# flight_cont_card.net
KiCad netlist of a schematic drawn in Altium Designer
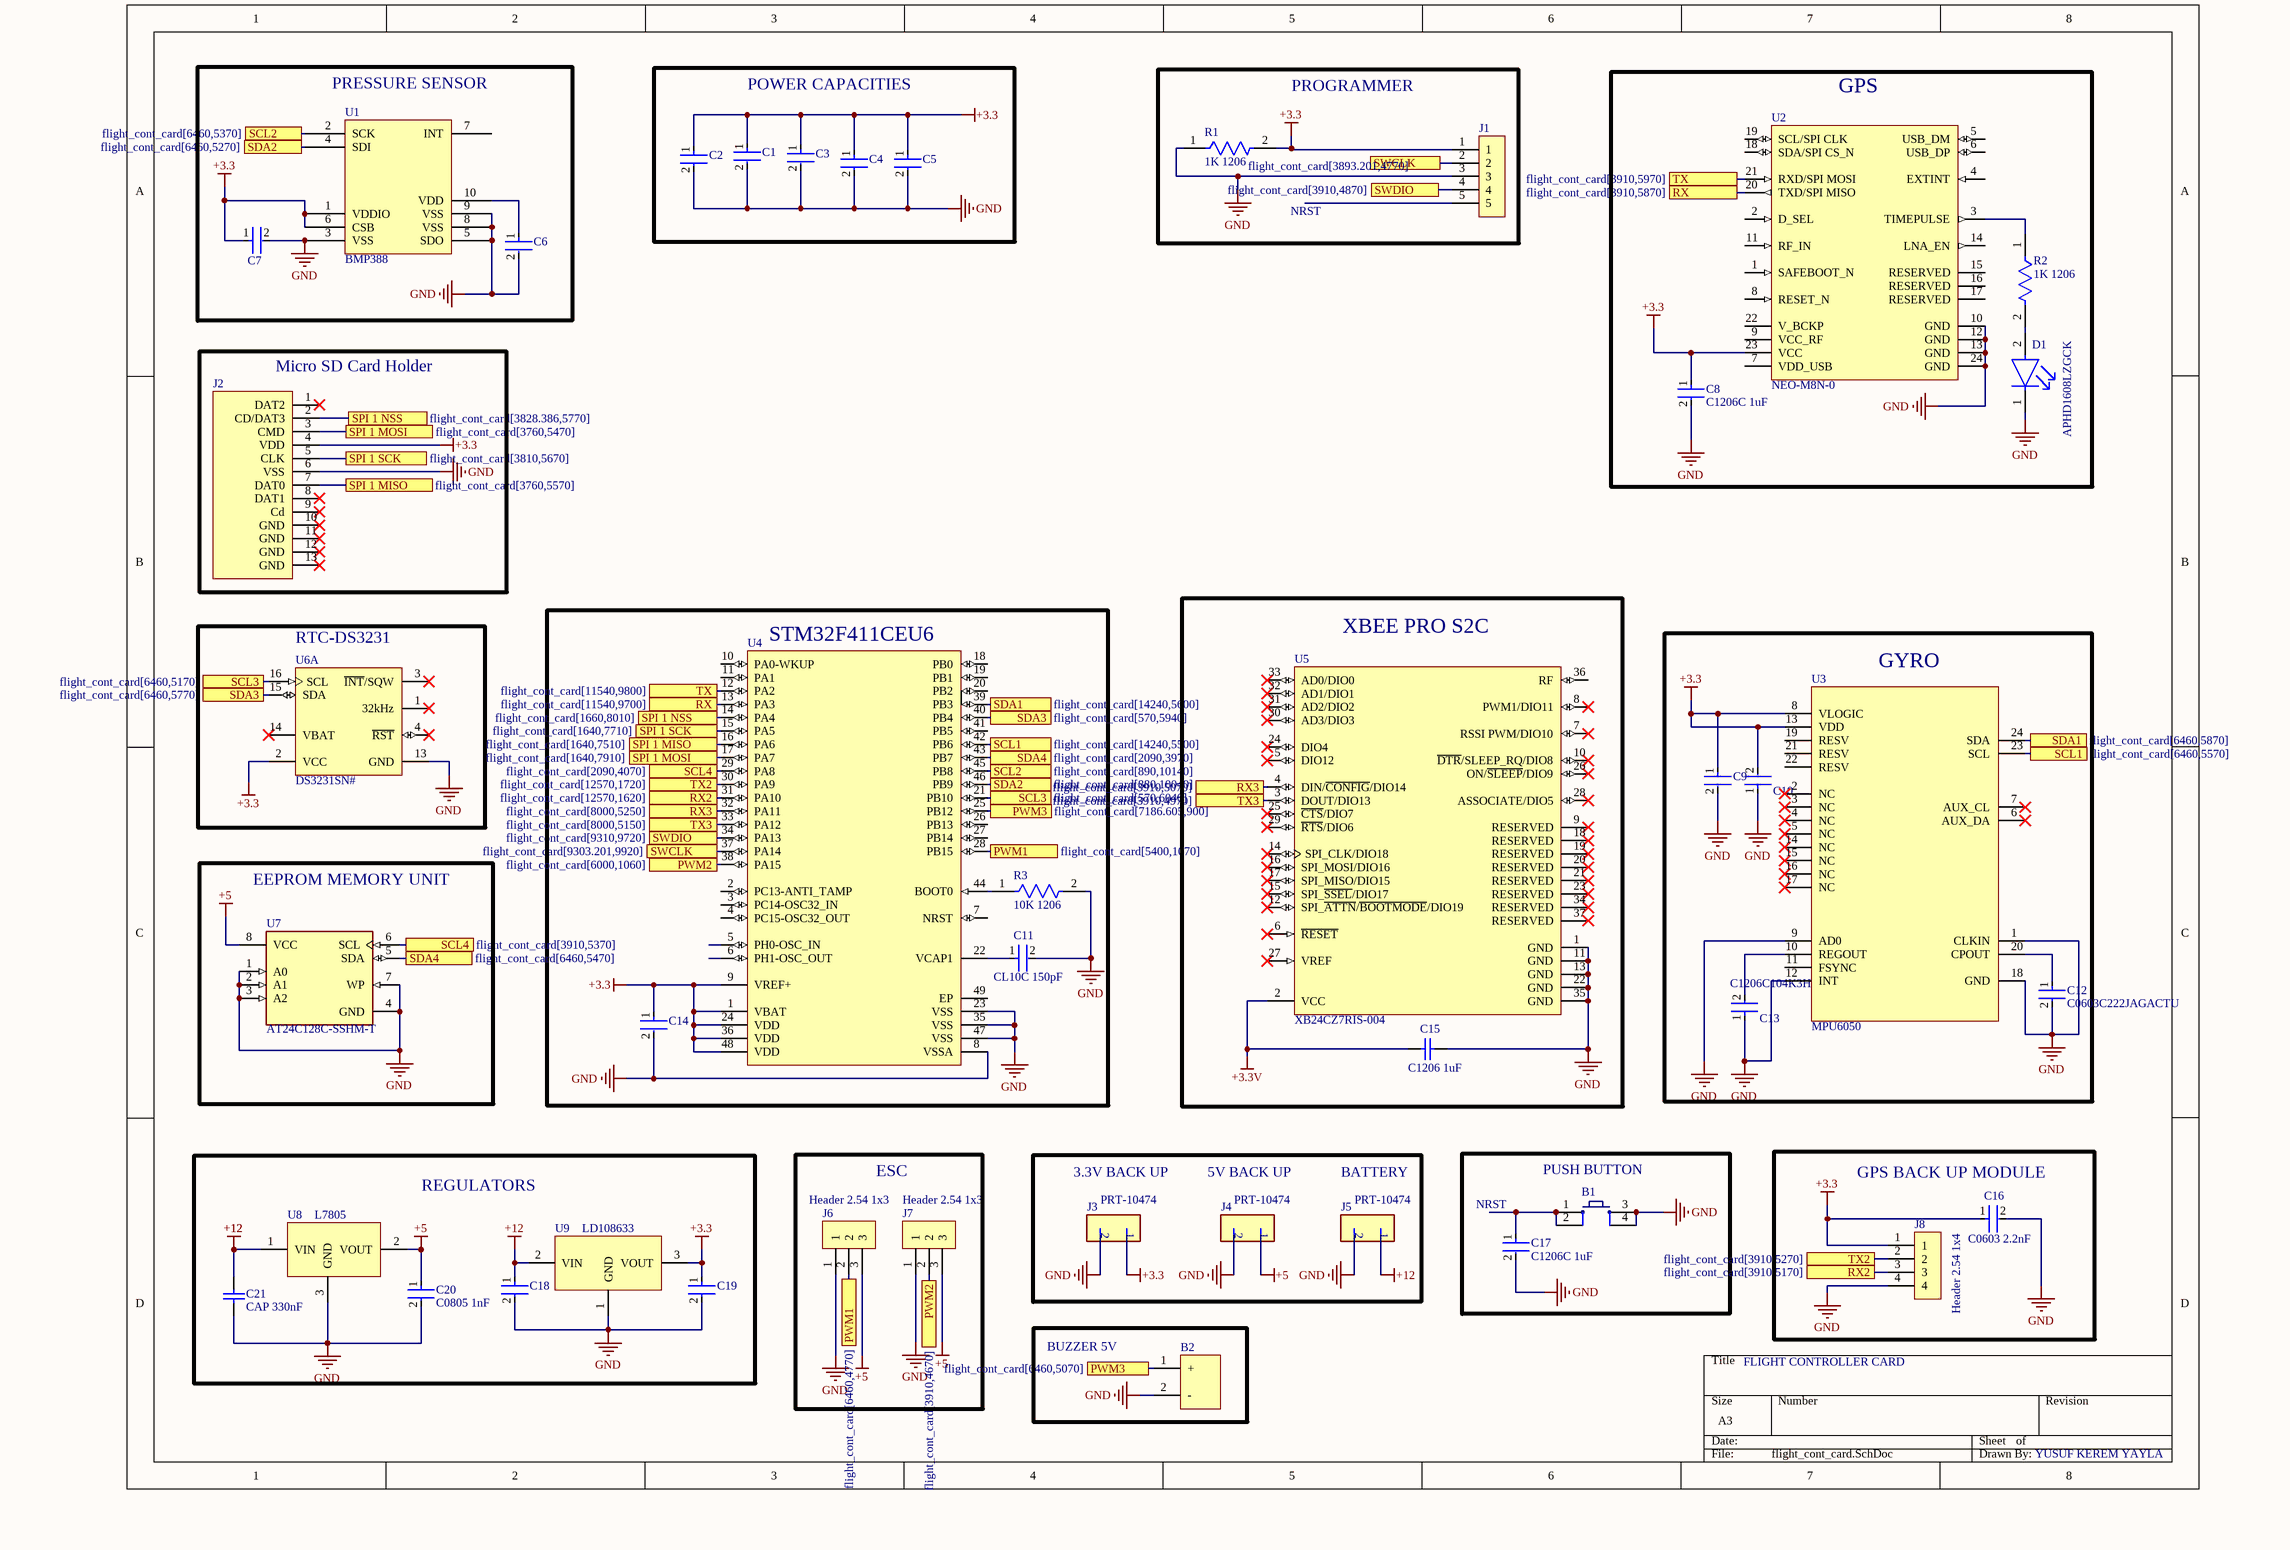
[diagram p0: flight_cont_card.SchDoc]

(export (version "E")
  (design (tool "Eeschema 10.0.6"))
  (components
    (comp (ref "B1")
      (value "PUSH BUTTON")
      (footprint "PUSB BUTTON-SMD")
      (description "Smd Push Button")
      (libsource (lib "Stm32") (part "Push Button"))
    )
    (comp (ref "B2")
      (value "BUZZER 5V")
      (footprint "Buzzer 5v")
      (description "Buzzer 5v")
      (libsource (lib "Stm32") (part "Buzzer 5v"))
    )
    (comp (ref "C1")
      (value "CGA5L1X7R1E106K160AC")
      (footprint "FP-CGA5L-0_3-0_1-IPC_B")
      (description "Cap Ceramic 10uF 25V X7R 10% Pad SMD 1206 +125°C Automotive T/R")
      (fields (field (name "TOLERANCE") "10%"))
      (libsource (lib "Altium Content Vault") (part "b4654b650e69147ec39a6b967a45e02"))
    )
    (comp (ref "C2")
      (value "CGA5L1X7R1E106K160AC")
      (footprint "FP-CGA5L-0_3-0_1-IPC_B")
      (description "Cap Ceramic 10uF 25V X7R 10% Pad SMD 1206 +125°C Automotive T/R")
      (fields (field (name "TOLERANCE") "10%"))
      (libsource (lib "Altium Content Vault") (part "b4654b650e69147ec39a6b967a45e02"))
    )
    (comp (ref "C3")
      (value "CGA5L1X7R1E106K160AC")
      (footprint "FP-CGA5L-0_3-0_1-IPC_B")
      (description "Cap Ceramic 10uF 25V X7R 10% Pad SMD 1206 +125°C Automotive T/R")
      (fields (field (name "TOLERANCE") "10%"))
      (libsource (lib "Altium Content Vault") (part "b4654b650e69147ec39a6b967a45e02"))
    )
    (comp (ref "C4")
      (value "CGA5L1X7R1E106K160AC")
      (footprint "FP-CGA5L-0_3-0_1-IPC_B")
      (description "Cap Ceramic 10uF 25V X7R 10% Pad SMD 1206 +125°C Automotive T/R")
      (fields (field (name "TOLERANCE") "10%"))
      (libsource (lib "Altium Content Vault") (part "b4654b650e69147ec39a6b967a45e02"))
    )
    (comp (ref "C5")
      (value "CGA5L1X7R1E106K160AC")
      (footprint "FP-CGA5L-0_3-0_1-IPC_B")
      (description "Cap Ceramic 10uF 25V X7R 10% Pad SMD 1206 +125°C Automotive T/R")
      (fields (field (name "TOLERANCE") "10%"))
      (libsource (lib "Altium Content Vault") (part "b4654b650e69147ec39a6b967a45e02"))
    )
    (comp (ref "C6")
      (value "CGA5L1X7R1E106K160AC")
      (footprint "FP-CGA5L-0_3-0_1-IPC_B")
      (description "Cap Ceramic 10uF 25V X7R 10% Pad SMD 1206 +125°C Automotive T/R")
      (fields (field (name "TOLERANCE") "10%"))
      (libsource (lib "Altium Content Vault") (part "b4654b650e69147ec39a6b967a45e02"))
    )
    (comp (ref "C7")
      (value "CGA5L1X7R1E106K160AC")
      (footprint "FP-CGA5L-0_3-0_1-IPC_B")
      (description "Cap Ceramic 10uF 25V X7R 10% Pad SMD 1206 +125°C Automotive T/R")
      (fields (field (name "TOLERANCE") "10%"))
      (libsource (lib "Altium Content Vault") (part "b4654b650e69147ec39a6b967a45e02"))
    )
    (comp (ref "C8")
      (value "C1206C 1uF")
      (footprint "FP-C1206C-EB-MFG")
      (description "CAP CER 0.1UF 200V X7R 1206")
      (fields
        (field (name "MANUFACTURER") "KEMET")
        (field (name "MANUFACTURER PART NUMBER") "C1206C104J2RACTU")
      )
      (libsource (lib "Altium Content Vault") (part "b4654b650e69147ec39a6b967a45e02"))
    )
    (comp (ref "C9")
      (value "C1206C104K3HACTU")
      (footprint "FP-C1206C-EB-MFG")
      (description "CAP CER 0.1UF 25V X8R 1206")
      (fields (field (name "MANUFACTURER") "KEMET") (field (name "TOLERANCE") "0.1"))
      (libsource (lib "Altium Content Vault") (part "b4654b650e69147ec39a6b967a45e02"))
    )
    (comp (ref "C10")
      (value "C1206C104K3HACTU")
      (footprint "FP-C1206C-EB-MFG")
      (description "CAP CER 0.1UF 25V X8R 1206")
      (fields (field (name "MANUFACTURER") "KEMET") (field (name "TOLERANCE") "0.1"))
      (libsource (lib "Altium Content Vault") (part "b4654b650e69147ec39a6b967a45e02"))
    )
    (comp (ref "C11")
      (value "CL10C 150pF")
      (footprint "FP-CL10-IPC_A")
      (description "Cap Ceramic 150pF 50V C0G ±5% Pad SMD 0603 +125°C T/R")
      (fields (field (name "TOLERANCE") "5%"))
      (libsource (lib "Altium Content Vault") (part "b4654b650e69147ec39a6b967a45e02"))
    )
    (comp (ref "C12")
      (value "C0603C222JAGACTU")
      (footprint "FP-C0603C-CF-MFG")
      (description "C0603 2,200 pF C0G 30ppm/°C 5.00% 250 V")
      (fields (field (name "MANUFACTURER") "KEMET") (field (name "TOLERANCE") "0.05"))
      (libsource (lib "Altium Content Vault") (part "b4654b650e69147ec39a6b967a45e02"))
    )
    (comp (ref "C13")
      (value "C1206C104K3HACTU")
      (footprint "FP-C1206C-EB-MFG")
      (description "0.1 uF")
      (fields (field (name "MANUFACTURER") "KEMET") (field (name "TOLERANCE") "0.1"))
      (libsource (lib "Altium Content Vault") (part "b4654b650e69147ec39a6b967a45e02"))
    )
    (comp (ref "C14")
      (value "08051C105K4T2A")
      (footprint "FP-0805-L_2_01_0_2-W_1_25-MFG")
      (description "08051C105K4T2A Cap Ceramic 1uF 100V X7R 10% Pad SMD 0805 125C Automotive T/R")
      (fields (field (name "TOLERANCE") "10%"))
      (libsource (lib "Altium Content Vault") (part "b4654b650e69147ec39a6b967a45e02"))
    )
    (comp (ref "C15")
      (value "C1206 1uF")
      (footprint "CAPC3216X180X50ML20T25")
      (description "Chip Capacitor, 1 uF, +/- 10%, 25 V, -55 to 125 degC, 1206 (3216 Metric), RoHS, Tape and Reel")
      (fields (field (name "MANUFACTURER") "Kemet") (field (name "TOLERANCE") "10%"))
      (libsource (lib "Altium Content Vault") (part "CAP-NP-2"))
    )
    (comp (ref "C16")
      (value "C0603 2.2nF")
      (footprint "FP-C0603C-CF-MFG")
      (description "C0603 2,200 pF C0G 30ppm/°C 5.00% 250 V")
      (fields
        (field (name "MANUFACTURER PART NUMBER") "C0603C222JAGACTU")
        (field (name "MANUFACTURER") "KEMET")
      )
      (libsource (lib "Altium Content Vault") (part "b4654b650e69147ec39a6b967a45e02"))
    )
    (comp (ref "C17")
      (value "C1206C 1uF")
      (footprint "FP-C1206C-EB-MFG")
      (description "CAP CER 0.1UF 200V X7R 1206")
      (fields
        (field (name "MANUFACTURER") "KEMET")
        (field (name "MANUFACTURER PART NUMBER") "C1206C104J2RACTU")
      )
      (libsource (lib "Altium Content Vault") (part "b4654b650e69147ec39a6b967a45e02"))
    )
    (comp (ref "C18")
      (value "CGA5L1X7R1E106K160AC")
      (footprint "FP-CGA5L-0_3-0_1-IPC_B")
      (description "Cap Ceramic 10uF 25V X7R 10% Pad SMD 1206 +125°C Automotive T/R")
      (fields (field (name "TOLERANCE") "10%"))
      (libsource (lib "Altium Content Vault") (part "b4654b650e69147ec39a6b967a45e02"))
    )
    (comp (ref "C19")
      (value "CGA5L1X7R1E106K160AC")
      (footprint "FP-CGA5L-0_3-0_1-IPC_B")
      (description "Cap Ceramic 10uF 25V X7R 10% Pad SMD 1206 +125°C Automotive T/R")
      (fields (field (name "TOLERANCE") "10%"))
      (libsource (lib "Altium Content Vault") (part "b4654b650e69147ec39a6b967a45e02"))
    )
    (comp (ref "C20")
      (value "C0805 1nF")
      (footprint "FP-C0805C-DN-MFG")
      (description "CAP CER 1000PF 100V X7R 0805")
      (fields
        (field (name "OCTOPART") "https://octopart.com/c0805c102m1ractu-kemet-9143290")
        (field (name "MANUFACTURER PART NUMBER") "C0805C102M1RACTU")
      )
      (libsource (lib "Altium Content Vault") (part "b4654b650e69147ec39a6b967a45e02"))
    )
    (comp (ref "C21")
      (value "CAP 330nF")
      (footprint "CAPC2220(5750)190_N")
      (description "CAP 330nF 100V ±10% 2220 (5750 Metric) Thickness 1.85mm SMD")
      (fields (field (name "TOLERANCE") "Â±10%"))
      (libsource (lib "Altium Content Vault") (part "CAP"))
    )
    (comp (ref "D1")
      (value "APHD1608LZGCK")
      (footprint "FP-APHD1608LZGCK-MFG")
      (description "LED GREEN CLEAR 1608 SMD")
      (libsource (lib "Altium Content Vault") (part "8706943c75ba83719d021d2fdc84c58"))
    )
    (comp (ref "J1")
      (value "Header 2.54 1x5")
      (footprint "Header 2.54 1x5")
      (libsource (lib "Stm32") (part "Header 2.54 1x5"))
    )
    (comp (ref "J2")
      (value "Micro SD Card Holder")
      (footprint "Micro SD Card Holder")
      (libsource (lib "Stm32") (part "Micro SD Card Holder"))
    )
    (comp (ref "J3")
      (value "PRT-10474")
      (footprint "FP-PRT-10474-MFG")
      (description "XT60 CONNECTORS MALE/FEMALE PAIR")
      (libsource (lib "Altium Content Vault") (part "e9d95e9eb6564353a08a501d7ea6c79"))
    )
    (comp (ref "J4")
      (value "PRT-10474")
      (footprint "FP-PRT-10474-MFG")
      (description "XT60 CONNECTORS MALE/FEMALE PAIR")
      (libsource (lib "Altium Content Vault") (part "e9d95e9eb6564353a08a501d7ea6c79"))
    )
    (comp (ref "J5")
      (value "PRT-10474")
      (footprint "FP-PRT-10474-MFG")
      (description "XT60 CONNECTORS MALE/FEMALE PAIR")
      (libsource (lib "Altium Content Vault") (part "e9d95e9eb6564353a08a501d7ea6c79"))
    )
    (comp (ref "J6")
      (value "Header 2.54 1x3")
      (footprint "Header 2.54 1x3")
      (libsource (lib "Stm32") (part "Header 2.54 1x3"))
    )
    (comp (ref "J7")
      (value "Header 2.54 1x3")
      (footprint "Header 2.54 1x3")
      (libsource (lib "Stm32") (part "Header 2.54 1x3"))
    )
    (comp (ref "J8")
      (value "Header 2.54 1x4")
      (footprint "Header 2.54 1x4")
      (libsource (lib "Stm32") (part "Header 2.54 1x4"))
    )
    (comp (ref "R1")
      (value "1K 1206")
      (footprint "FP-RMCF1206-IPC_A")
      (description "1kΩ ±5% 0.25W 1206 Thick Film Chip Resistor AEC-Q200 compliant")
      (fields (field (name "TOLERANCE") "5%"))
      (libsource (lib "Altium Content Vault") (part "1029c3af85768c4190bb7ad29bc67b5"))
    )
    (comp (ref "R2")
      (value "1K 1206")
      (footprint "FP-RMCF1206-IPC_A")
      (description "1kΩ ±5% 0.25W 1206 Thick Film Chip Resistor AEC-Q200 compliant")
      (fields (field (name "TOLERANCE") "5%"))
      (libsource (lib "Altium Content Vault") (part "1029c3af85768c4190bb7ad29bc67b5"))
    )
    (comp (ref "R3")
      (value "10K 1206")
      (footprint "FP-CRGP1206-IPC_C")
      (description "CRGP 1206 10K 1%")
      (fields
        (field (name "OCTOPART") "https://octopart.com/crgp1206f10k-te+connectivity-91018843")
        (field (name "MANUFACTURER PART NUMBER") "CRGP1206F10K")
      )
      (libsource (lib "Altium Content Vault") (part "1029c3af85768c4190bb7ad29bc67b5"))
    )
    (comp (ref "U1") (value "BMP388") (footprint "BMP388") (libsource (lib "Stm32") (part "BMP388")))
    (comp (ref "U2")
      (value "NEO-M8N-0")
      (footprint "UBX-NEO-M8-24_V")
      (description "U-Blox M8 Concurrent Gnss Module, 3.6 V, -40 to 85 degC, 24-Pin SMD, RoHS, Tape and Reel")
      (fields (field (name "MANUFACTURER") "U-Blox"))
      (libsource (lib "Altium Content Vault") (part "UBX-NEO-M8X-24"))
    )
    (comp (ref "U3")
      (value "MPU6050")
      (footprint "QFN50P400X400X90_HS-25N")
      (description "MPU6050 GYRO")
      (libsource (lib "Stm32") (part "MPU6050"))
    )
    (comp (ref "U4")
      (value "STM32F411CEU6")
      (footprint "STM-UFQFPN48_L")
      (libsource (lib "Altium Content Vault") (part "MC-ARM-STM32F411-UFQFPN48"))
    )
    (comp (ref "U5")
      (value "XB24CZ7RIS-004")
      (footprint "DIGI-XB24CZ7RIS-004-Module-37_V")
      (fields (field (name "MANUFACTURER") "Digi international"))
      (libsource (lib "Altium Content Vault") (part "DIGI-XB24CZ7RIS-004-Module-37"))
    )
    (comp (ref "U6")
      (value "DS3231SN#")
      (footprint "W16#H2_L")
      (libsource (lib "Altium Content Vault") (part "MAX-RTC-16-DS3231S-W16#H2"))
    )
    (comp (ref "U7")
      (value "AT24C128C-SSHM-T")
      (footprint "FP-C04-057-SN-IPC_A")
      (description "IC EEPROM 128K I2C 1MHZ 8SOIC")
      (libsource (lib "Altium Content Vault") (part "2a7f6fd195537f93883cbf726a7dbe1"))
    )
    (comp (ref "U8")
      (value "L7805")
      (footprint "DPAK228P972X230-3N")
      (description "L7805 5V REGULATOR. SMD PAKET")
      (libsource (lib "Stm32") (part "L7805-DPAK"))
    )
    (comp (ref "U9")
      (value "LD108633")
      (footprint "DPAK228P972X230-3N")
      (description "LD1086 3.3V REGULATOR")
      (libsource (lib "Stm32") (part "LD108633 DPAK"))
    )
  )
  (nets
    (net (code "1") (name "+3.3") (class "Default")
      (node (ref "C1") (pin "1") (pinfunction "1_1") (pintype "passive"))
      (node (ref "C10") (pin "2") (pinfunction "2_2") (pintype "passive"))
      (node (ref "C14") (pin "1") (pinfunction "1_1") (pintype "passive"))
      (node (ref "C16") (pin "1") (pinfunction "1_1") (pintype "passive"))
      (node (ref "C19") (pin "1") (pinfunction "1_1") (pintype "passive"))
      (node (ref "C2") (pin "1") (pinfunction "1_1") (pintype "passive"))
      (node (ref "C3") (pin "1") (pinfunction "1_1") (pintype "passive"))
      (node (ref "C4") (pin "1") (pinfunction "1_1") (pintype "passive"))
      (node (ref "C5") (pin "1") (pinfunction "1_1") (pintype "passive"))
      (node (ref "C7") (pin "1") (pinfunction "1_1") (pintype "passive"))
      (node (ref "C8") (pin "1") (pinfunction "1_1") (pintype "passive"))
      (node (ref "C9") (pin "1") (pinfunction "1_1") (pintype "passive"))
      (node (ref "J1") (pin "1") (pinfunction "1_1") (pintype "passive"))
      (node (ref "J2") (pin "4") (pinfunction "VDD_4") (pintype "passive"))
      (node (ref "J8") (pin "1") (pinfunction "1_1") (pintype "passive"))
      (node (ref "R1") (pin "2") (pinfunction "2_2") (pintype "passive"))
      (node (ref "U1") (pin "1") (pinfunction "VDDIO_1") (pintype "passive"))
      (node (ref "U1") (pin "6") (pinfunction "CSB_6") (pintype "passive"))
      (node (ref "U2") (pin "23") (pinfunction "VCC_23") (pintype "power_in"))
      (node (ref "U3") (pin "13") (pinfunction "VDD_13") (pintype "passive"))
      (node (ref "U3") (pin "8") (pinfunction "VLOGIC_8") (pintype "passive"))
      (node (ref "U4") (pin "1") (pinfunction "VBAT_1") (pintype "power_in"))
      (node (ref "U4") (pin "24") (pinfunction "VDD_24") (pintype "power_in"))
      (node (ref "U4") (pin "36") (pinfunction "VDD_36") (pintype "power_in"))
      (node (ref "U4") (pin "48") (pinfunction "VDD_48") (pintype "power_in"))
      (node (ref "U4") (pin "9") (pinfunction "VREF+_9") (pintype "power_in"))
      (node (ref "U6") (pin "2") (pinfunction "VCC_2") (pintype "power_in"))
      (node (ref "U9") (pin "3") (pinfunction "VOUT_3") (pintype "passive"))
    )
    (net (code "2") (name "+3.3V") (class "Default")
      (node (ref "C15") (pin "1") (pinfunction "1_1") (pintype "passive"))
      (node (ref "U5") (pin "2") (pinfunction "VCC_2") (pintype "power_in"))
    )
    (net (code "3") (name "+5") (class "Default")
      (node (ref "C20") (pin "1") (pinfunction "1_1") (pintype "passive"))
      (node (ref "J6") (pin "3") (pinfunction "3_3") (pintype "passive"))
      (node (ref "J7") (pin "3") (pinfunction "3_3") (pintype "passive"))
      (node (ref "U7") (pin "8") (pinfunction "VCC_8") (pintype "power_in"))
      (node (ref "U8") (pin "2") (pinfunction "VOUT_2") (pintype "passive"))
    )
    (net (code "4") (name "+12") (class "Default")
      (node (ref "C18") (pin "1") (pinfunction "1_1") (pintype "passive"))
      (node (ref "C21") (pin "2") (pinfunction "2_2") (pintype "passive"))
      (node (ref "U8") (pin "1") (pinfunction "VIN_1") (pintype "passive"))
      (node (ref "U9") (pin "2") (pinfunction "VIN_2") (pintype "passive"))
    )
    (net (code "5") (name "/PWM1") (class "Default")
      (node (ref "J6") (pin "2") (pinfunction "2_2") (pintype "passive"))
      (node (ref "U4") (pin "28") (pinfunction "PB15_28") (pintype "bidirectional"))
    )
    (net (code "6") (name "/PWM2") (class "Default")
      (node (ref "J7") (pin "2") (pinfunction "2_2") (pintype "passive"))
      (node (ref "U4") (pin "38") (pinfunction "PA15_38") (pintype "bidirectional"))
    )
    (net (code "7") (name "/PWM3") (class "Default")
      (node (ref "B2") (pin "1") (pinfunction "+_1") (pintype "passive"))
      (node (ref "U4") (pin "25") (pinfunction "PB12_25") (pintype "bidirectional"))
    )
    (net (code "8") (name "/RX") (class "Default")
      (node (ref "U2") (pin "20") (pinfunction "TXD/SPI_MISO_20") (pintype "output"))
      (node (ref "U4") (pin "13") (pinfunction "PA3_13") (pintype "bidirectional"))
    )
    (net (code "9") (name "/RX2") (class "Default")
      (node (ref "J8") (pin "3") (pinfunction "3_3") (pintype "passive"))
      (node (ref "U4") (pin "31") (pinfunction "PA10_31") (pintype "bidirectional"))
    )
    (net (code "10") (name "/RX3") (class "Default")
      (node (ref "U4") (pin "32") (pinfunction "PA11_32") (pintype "bidirectional"))
      (node (ref "U5") (pin "4") (pinfunction "DIN/~{CONFIG}/DIO14_4") (pintype "bidirectional"))
    )
    (net (code "11") (name "/SCL1") (class "Default")
      (node (ref "U3") (pin "23") (pinfunction "SCL_23") (pintype "passive"))
      (node (ref "U4") (pin "42") (pinfunction "PB6_42") (pintype "bidirectional"))
    )
    (net (code "12") (name "/SCL2") (class "Default")
      (node (ref "U1") (pin "2") (pinfunction "SCK_2") (pintype "passive"))
      (node (ref "U4") (pin "45") (pinfunction "PB8_45") (pintype "bidirectional"))
    )
    (net (code "13") (name "/SCL3") (class "Default")
      (node (ref "U4") (pin "21") (pinfunction "PB10_21") (pintype "bidirectional"))
      (node (ref "U6") (pin "16") (pinfunction "SCL_16") (pintype "input"))
    )
    (net (code "14") (name "/SCL4") (class "Default")
      (node (ref "U4") (pin "29") (pinfunction "PA8_29") (pintype "bidirectional"))
      (node (ref "U7") (pin "6") (pinfunction "SCL_6") (pintype "input"))
    )
    (net (code "15") (name "/SDA1") (class "Default")
      (node (ref "U3") (pin "24") (pinfunction "SDA_24") (pintype "passive"))
      (node (ref "U4") (pin "39") (pinfunction "PB3_39") (pintype "bidirectional"))
    )
    (net (code "16") (name "/SDA2") (class "Default")
      (node (ref "U1") (pin "4") (pinfunction "SDI_4") (pintype "passive"))
      (node (ref "U4") (pin "46") (pinfunction "PB9_46") (pintype "bidirectional"))
    )
    (net (code "17") (name "/SDA3") (class "Default")
      (node (ref "U4") (pin "40") (pinfunction "PB4_40") (pintype "bidirectional"))
      (node (ref "U6") (pin "15") (pinfunction "SDA_15") (pintype "bidirectional"))
    )
    (net (code "18") (name "/SDA4") (class "Default")
      (node (ref "U4") (pin "43") (pinfunction "PB7_43") (pintype "bidirectional"))
      (node (ref "U7") (pin "5") (pinfunction "SDA_5") (pintype "bidirectional"))
    )
    (net (code "19") (name "/SPI 1 MISO") (class "Default")
      (node (ref "J2") (pin "7") (pinfunction "DAT0_7") (pintype "passive"))
      (node (ref "U4") (pin "16") (pinfunction "PA6_16") (pintype "bidirectional"))
    )
    (net (code "20") (name "/SPI 1 MOSI") (class "Default")
      (node (ref "J2") (pin "3") (pinfunction "CMD_3") (pintype "passive"))
      (node (ref "U4") (pin "17") (pinfunction "PA7_17") (pintype "bidirectional"))
    )
    (net (code "21") (name "/SPI 1 NSS") (class "Default")
      (node (ref "J2") (pin "2") (pinfunction "CD/DAT3_2") (pintype "passive"))
      (node (ref "U4") (pin "14") (pinfunction "PA4_14") (pintype "bidirectional"))
    )
    (net (code "22") (name "/SPI 1 SCK") (class "Default")
      (node (ref "J2") (pin "5") (pinfunction "CLK_5") (pintype "passive"))
      (node (ref "U4") (pin "15") (pinfunction "PA5_15") (pintype "bidirectional"))
    )
    (net (code "23") (name "/SWCLK") (class "Default")
      (node (ref "J1") (pin "2") (pinfunction "2_2") (pintype "passive"))
      (node (ref "U4") (pin "37") (pinfunction "PA14_37") (pintype "bidirectional"))
    )
    (net (code "24") (name "/SWDIO") (class "Default")
      (node (ref "J1") (pin "4") (pinfunction "4_4") (pintype "passive"))
      (node (ref "U4") (pin "34") (pinfunction "PA13_34") (pintype "bidirectional"))
    )
    (net (code "25") (name "/TX") (class "Default")
      (node (ref "U2") (pin "21") (pinfunction "RXD/SPI_MOSI_21") (pintype "input"))
      (node (ref "U4") (pin "12") (pinfunction "PA2_12") (pintype "bidirectional"))
    )
    (net (code "26") (name "/TX2") (class "Default")
      (node (ref "J8") (pin "2") (pinfunction "2_2") (pintype "passive"))
      (node (ref "U4") (pin "30") (pinfunction "PA9_30") (pintype "bidirectional"))
    )
    (net (code "27") (name "/TX3") (class "Default")
      (node (ref "U4") (pin "33") (pinfunction "PA12_33") (pintype "bidirectional"))
      (node (ref "U5") (pin "3") (pinfunction "DOUT/DIO13_3") (pintype "bidirectional"))
    )
    (net (code "28") (name "GND") (class "Default")
      (node (ref "B1") (pin "3") (pinfunction "3_3") (pintype "passive"))
      (node (ref "B1") (pin "4") (pinfunction "4_4") (pintype "passive"))
      (node (ref "B2") (pin "2") (pinfunction "-_2") (pintype "passive"))
      (node (ref "C1") (pin "2") (pinfunction "2_2") (pintype "passive"))
      (node (ref "C10") (pin "1") (pinfunction "1_1") (pintype "passive"))
      (node (ref "C11") (pin "2") (pinfunction "2_2") (pintype "passive"))
      (node (ref "C12") (pin "2") (pinfunction "2_2") (pintype "passive"))
      (node (ref "C13") (pin "1") (pinfunction "1_1") (pintype "passive"))
      (node (ref "C14") (pin "2") (pinfunction "2_2") (pintype "passive"))
      (node (ref "C15") (pin "2") (pinfunction "2_2") (pintype "passive"))
      (node (ref "C16") (pin "2") (pinfunction "2_2") (pintype "passive"))
      (node (ref "C17") (pin "2") (pinfunction "2_2") (pintype "passive"))
      (node (ref "C18") (pin "2") (pinfunction "2_2") (pintype "passive"))
      (node (ref "C19") (pin "2") (pinfunction "2_2") (pintype "passive"))
      (node (ref "C2") (pin "2") (pinfunction "2_2") (pintype "passive"))
      (node (ref "C20") (pin "2") (pinfunction "2_2") (pintype "passive"))
      (node (ref "C21") (pin "1") (pinfunction "1_1") (pintype "passive"))
      (node (ref "C3") (pin "2") (pinfunction "2_2") (pintype "passive"))
      (node (ref "C4") (pin "2") (pinfunction "2_2") (pintype "passive"))
      (node (ref "C5") (pin "2") (pinfunction "2_2") (pintype "passive"))
      (node (ref "C6") (pin "2") (pinfunction "2_2") (pintype "passive"))
      (node (ref "C7") (pin "2") (pinfunction "2_2") (pintype "passive"))
      (node (ref "C8") (pin "2") (pinfunction "2_2") (pintype "passive"))
      (node (ref "C9") (pin "2") (pinfunction "2_2") (pintype "passive"))
      (node (ref "D1") (pin "1") (pinfunction "C_1") (pintype "passive"))
      (node (ref "J1") (pin "3") (pinfunction "3_3") (pintype "passive"))
      (node (ref "J2") (pin "6") (pinfunction "VSS_6") (pintype "passive"))
      (node (ref "J6") (pin "1") (pinfunction "1_1") (pintype "passive"))
      (node (ref "J7") (pin "1") (pinfunction "1_1") (pintype "passive"))
      (node (ref "J8") (pin "4") (pinfunction "4_4") (pintype "passive"))
      (node (ref "R1") (pin "1") (pinfunction "1_1") (pintype "passive"))
      (node (ref "R3") (pin "2") (pinfunction "2_2") (pintype "passive"))
      (node (ref "U1") (pin "3") (pinfunction "VSS_3") (pintype "passive"))
      (node (ref "U1") (pin "5") (pinfunction "SDO_5") (pintype "passive"))
      (node (ref "U1") (pin "8") (pinfunction "VSS_8") (pintype "passive"))
      (node (ref "U1") (pin "9") (pinfunction "VSS_9") (pintype "passive"))
      (node (ref "U2") (pin "10") (pinfunction "GND_10") (pintype "power_in"))
      (node (ref "U2") (pin "12") (pinfunction "GND_12") (pintype "power_in"))
      (node (ref "U2") (pin "13") (pinfunction "GND_13") (pintype "power_in"))
      (node (ref "U2") (pin "24") (pinfunction "GND_24") (pintype "power_in"))
      (node (ref "U3") (pin "1") (pinfunction "CLKIN_1") (pintype "passive"))
      (node (ref "U3") (pin "12") (pinfunction "INT_12") (pintype "passive"))
      (node (ref "U3") (pin "18") (pinfunction "GND_18") (pintype "passive"))
      (node (ref "U3") (pin "9") (pinfunction "AD0_9") (pintype "passive"))
      (node (ref "U4") (pin "23") (pinfunction "VSS_23") (pintype "power_in"))
      (node (ref "U4") (pin "35") (pinfunction "VSS_35") (pintype "power_in"))
      (node (ref "U4") (pin "47") (pinfunction "VSS_47") (pintype "power_in"))
      (node (ref "U4") (pin "8") (pinfunction "VSSA_8") (pintype "power_in"))
      (node (ref "U5") (pin "1") (pinfunction "GND_1") (pintype "power_in"))
      (node (ref "U5") (pin "11") (pinfunction "GND_11") (pintype "power_in"))
      (node (ref "U5") (pin "13") (pinfunction "GND_13") (pintype "power_in"))
      (node (ref "U5") (pin "22") (pinfunction "GND_22") (pintype "power_in"))
      (node (ref "U5") (pin "35") (pinfunction "GND_35") (pintype "power_in"))
      (node (ref "U6") (pin "13") (pinfunction "GND_13") (pintype "power_in"))
      (node (ref "U7") (pin "1") (pinfunction "A0_1") (pintype "input"))
      (node (ref "U7") (pin "2") (pinfunction "A1_2") (pintype "input"))
      (node (ref "U7") (pin "3") (pinfunction "A2_3") (pintype "input"))
      (node (ref "U7") (pin "4") (pinfunction "GND_4") (pintype "power_in"))
      (node (ref "U7") (pin "7") (pinfunction "WP_7") (pintype "input"))
      (node (ref "U8") (pin "3") (pinfunction "GND_3") (pintype "passive"))
      (node (ref "U9") (pin "1") (pinfunction "GND_1") (pintype "passive"))
    )
    (net (code "29") (name "Net-(B1-Pad1)") (class "Default")
      (node (ref "B1") (pin "1") (pinfunction "1_1") (pintype "passive"))
      (node (ref "B1") (pin "2") (pinfunction "2_2") (pintype "passive"))
      (node (ref "C17") (pin "1") (pinfunction "1_1") (pintype "passive"))
    )
    (net (code "30") (name "Net-(D1-A)") (class "Default")
      (node (ref "D1") (pin "2") (pinfunction "A_2") (pintype "passive"))
      (node (ref "R2") (pin "2") (pinfunction "2_2") (pintype "passive"))
    )
    (net (code "31") (name "Net-(U1-VDD)") (class "Default")
      (node (ref "C6") (pin "1") (pinfunction "1_1") (pintype "passive"))
      (node (ref "U1") (pin "10") (pinfunction "VDD_10") (pintype "passive"))
    )
    (net (code "32") (name "Net-(U2-TIMEPULSE)") (class "Default")
      (node (ref "R2") (pin "1") (pinfunction "1_1") (pintype "passive"))
      (node (ref "U2") (pin "3") (pinfunction "TIMEPULSE_3") (pintype "output"))
    )
    (net (code "33") (name "Net-(U3-CPOUT)") (class "Default")
      (node (ref "C12") (pin "1") (pinfunction "1_1") (pintype "passive"))
      (node (ref "U3") (pin "20") (pinfunction "CPOUT_20") (pintype "passive"))
    )
    (net (code "34") (name "Net-(U3-REGOUT)") (class "Default")
      (node (ref "C13") (pin "2") (pinfunction "2_2") (pintype "passive"))
      (node (ref "U3") (pin "10") (pinfunction "REGOUT_10") (pintype "passive"))
    )
    (net (code "35") (name "Net-(U4-BOOT0)") (class "Default")
      (node (ref "R3") (pin "1") (pinfunction "1_1") (pintype "passive"))
      (node (ref "U4") (pin "44") (pinfunction "BOOT0_44") (pintype "input"))
    )
    (net (code "36") (name "Net-(U4-VCAP1)") (class "Default")
      (node (ref "C11") (pin "1") (pinfunction "1_1") (pintype "passive"))
      (node (ref "U4") (pin "22") (pinfunction "VCAP1_22") (pintype "passive"))
    )
    (net (code "37") (name "unconnected-(J1-Pad5)") (class "Default")
      (node (ref "J1") (pin "5") (pinfunction "5_5") (pintype "passive"))
    )
    (net (code "38") (name "unconnected-(J2-Cd-Pad9)") (class "Default")
      (node (ref "J2") (pin "9") (pinfunction "Cd_9") (pintype "passive+no_connect"))
    )
    (net (code "39") (name "unconnected-(J2-DAT1-Pad8)") (class "Default")
      (node (ref "J2") (pin "8") (pinfunction "DAT1_8") (pintype "passive+no_connect"))
    )
    (net (code "40") (name "unconnected-(J2-DAT2-Pad1)") (class "Default")
      (node (ref "J2") (pin "1") (pinfunction "DAT2_1") (pintype "passive+no_connect"))
    )
    (net (code "41") (name "unconnected-(J2-GND-Pad10)") (class "Default")
      (node (ref "J2") (pin "10") (pinfunction "GND_10") (pintype "passive+no_connect"))
    )
    (net (code "42") (name "unconnected-(J2-GND-Pad11)") (class "Default")
      (node (ref "J2") (pin "11") (pinfunction "GND_11") (pintype "passive+no_connect"))
    )
    (net (code "43") (name "unconnected-(J2-GND-Pad12)") (class "Default")
      (node (ref "J2") (pin "12") (pinfunction "GND_12") (pintype "passive+no_connect"))
    )
    (net (code "44") (name "unconnected-(J2-GND-Pad13)") (class "Default")
      (node (ref "J2") (pin "13") (pinfunction "GND_13") (pintype "passive+no_connect"))
    )
    (net (code "45") (name "unconnected-(U1-INT-Pad7)") (class "Default")
      (node (ref "U1") (pin "7") (pinfunction "INT_7") (pintype "passive"))
    )
    (net (code "46") (name "unconnected-(U2-D_SEL-Pad2)") (class "Default")
      (node (ref "U2") (pin "2") (pinfunction "D_SEL_2") (pintype "input"))
    )
    (net (code "47") (name "unconnected-(U2-EXTINT-Pad4)") (class "Default")
      (node (ref "U2") (pin "4") (pinfunction "EXTINT_4") (pintype "input"))
    )
    (net (code "48") (name "unconnected-(U2-LNA_EN-Pad14)") (class "Default")
      (node (ref "U2") (pin "14") (pinfunction "LNA_EN_14") (pintype "output"))
    )
    (net (code "49") (name "unconnected-(U2-RESERVED-Pad15)") (class "Default")
      (node (ref "U2") (pin "15") (pinfunction "RESERVED_15") (pintype "passive"))
    )
    (net (code "50") (name "unconnected-(U2-RESERVED-Pad16)") (class "Default")
      (node (ref "U2") (pin "16") (pinfunction "RESERVED_16") (pintype "passive"))
    )
    (net (code "51") (name "unconnected-(U2-RESERVED-Pad17)") (class "Default")
      (node (ref "U2") (pin "17") (pinfunction "RESERVED_17") (pintype "passive"))
    )
    (net (code "52") (name "unconnected-(U2-RESET_N-Pad8)") (class "Default")
      (node (ref "U2") (pin "8") (pinfunction "RESET_N_8") (pintype "input"))
    )
    (net (code "53") (name "unconnected-(U2-RF_IN-Pad11)") (class "Default")
      (node (ref "U2") (pin "11") (pinfunction "RF_IN_11") (pintype "input"))
    )
    (net (code "54") (name "unconnected-(U2-SAFEBOOT_N-Pad1)") (class "Default")
      (node (ref "U2") (pin "1") (pinfunction "SAFEBOOT_N_1") (pintype "input"))
    )
    (net (code "55") (name "unconnected-(U2-SCL{slash}SPI_CLK-Pad19)") (class "Default")
      (node (ref "U2") (pin "19") (pinfunction "SCL/SPI_CLK_19") (pintype "bidirectional"))
    )
    (net (code "56") (name "unconnected-(U2-SDA{slash}SPI_CS_N-Pad18)") (class "Default")
      (node (ref "U2") (pin "18") (pinfunction "SDA/SPI_CS_N_18") (pintype "bidirectional"))
    )
    (net (code "57") (name "unconnected-(U2-USB_DM-Pad5)") (class "Default")
      (node (ref "U2") (pin "5") (pinfunction "USB_DM_5") (pintype "bidirectional"))
    )
    (net (code "58") (name "unconnected-(U2-USB_DP-Pad6)") (class "Default")
      (node (ref "U2") (pin "6") (pinfunction "USB_DP_6") (pintype "bidirectional"))
    )
    (net (code "59") (name "unconnected-(U2-VCC_RF-Pad9)") (class "Default")
      (node (ref "U2") (pin "9") (pinfunction "VCC_RF_9") (pintype "power_in"))
    )
    (net (code "60") (name "unconnected-(U2-VDD_USB-Pad7)") (class "Default")
      (node (ref "U2") (pin "7") (pinfunction "VDD_USB_7") (pintype "power_in"))
    )
    (net (code "61") (name "unconnected-(U2-V_BCKP-Pad22)") (class "Default")
      (node (ref "U2") (pin "22") (pinfunction "V_BCKP_22") (pintype "power_in"))
    )
    (net (code "62") (name "unconnected-(U3-AUX_CL-Pad7)") (class "Default")
      (node (ref "U3") (pin "7") (pinfunction "AUX_CL_7") (pintype "passive+no_connect"))
    )
    (net (code "63") (name "unconnected-(U3-AUX_DA-Pad6)") (class "Default")
      (node (ref "U3") (pin "6") (pinfunction "AUX_DA_6") (pintype "passive+no_connect"))
    )
    (net (code "64") (name "unconnected-(U3-FSYNC-Pad11)") (class "Default")
      (node (ref "U3") (pin "11") (pinfunction "FSYNC_11") (pintype "passive"))
    )
    (net (code "65") (name "unconnected-(U3-NC-Pad2)") (class "Default")
      (node (ref "U3") (pin "2") (pinfunction "NC_2") (pintype "passive+no_connect"))
    )
    (net (code "66") (name "unconnected-(U3-NC-Pad3)") (class "Default")
      (node (ref "U3") (pin "3") (pinfunction "NC_3") (pintype "passive+no_connect"))
    )
    (net (code "67") (name "unconnected-(U3-NC-Pad4)") (class "Default")
      (node (ref "U3") (pin "4") (pinfunction "NC_4") (pintype "passive+no_connect"))
    )
    (net (code "68") (name "unconnected-(U3-NC-Pad5)") (class "Default")
      (node (ref "U3") (pin "5") (pinfunction "NC_5") (pintype "passive+no_connect"))
    )
    (net (code "69") (name "unconnected-(U3-NC-Pad14)") (class "Default")
      (node (ref "U3") (pin "14") (pinfunction "NC_14") (pintype "passive+no_connect"))
    )
    (net (code "70") (name "unconnected-(U3-NC-Pad15)") (class "Default")
      (node (ref "U3") (pin "15") (pinfunction "NC_15") (pintype "passive+no_connect"))
    )
    (net (code "71") (name "unconnected-(U3-NC-Pad16)") (class "Default")
      (node (ref "U3") (pin "16") (pinfunction "NC_16") (pintype "passive+no_connect"))
    )
    (net (code "72") (name "unconnected-(U3-NC-Pad17)") (class "Default")
      (node (ref "U3") (pin "17") (pinfunction "NC_17") (pintype "passive+no_connect"))
    )
    (net (code "73") (name "unconnected-(U3-RESV-Pad19)") (class "Default")
      (node (ref "U3") (pin "19") (pinfunction "RESV_19") (pintype "passive"))
    )
    (net (code "74") (name "unconnected-(U3-RESV-Pad21)") (class "Default")
      (node (ref "U3") (pin "21") (pinfunction "RESV_21") (pintype "passive"))
    )
    (net (code "75") (name "unconnected-(U3-RESV-Pad22)") (class "Default")
      (node (ref "U3") (pin "22") (pinfunction "RESV_22") (pintype "passive"))
    )
    (net (code "76") (name "unconnected-(U4-EP-Pad49)") (class "Default")
      (node (ref "U4") (pin "49") (pinfunction "EP_49") (pintype "power_in"))
    )
    (net (code "77") (name "unconnected-(U4-NRST-Pad7)") (class "Default")
      (node (ref "U4") (pin "7") (pinfunction "NRST_7") (pintype "bidirectional"))
    )
    (net (code "78") (name "unconnected-(U4-PA0-WKUP-Pad10)") (class "Default")
      (node (ref "U4") (pin "10") (pinfunction "PA0-WKUP_10") (pintype "bidirectional"))
    )
    (net (code "79") (name "unconnected-(U4-PA1-Pad11)") (class "Default")
      (node (ref "U4") (pin "11") (pinfunction "PA1_11") (pintype "bidirectional"))
    )
    (net (code "80") (name "unconnected-(U4-PB0-Pad18)") (class "Default")
      (node (ref "U4") (pin "18") (pinfunction "PB0_18") (pintype "bidirectional"))
    )
    (net (code "81") (name "unconnected-(U4-PB1-Pad19)") (class "Default")
      (node (ref "U4") (pin "19") (pinfunction "PB1_19") (pintype "bidirectional"))
    )
    (net (code "82") (name "unconnected-(U4-PB2-Pad20)") (class "Default")
      (node (ref "U4") (pin "20") (pinfunction "PB2_20") (pintype "bidirectional"))
    )
    (net (code "83") (name "unconnected-(U4-PB5-Pad41)") (class "Default")
      (node (ref "U4") (pin "41") (pinfunction "PB5_41") (pintype "bidirectional"))
    )
    (net (code "84") (name "unconnected-(U4-PB13-Pad26)") (class "Default")
      (node (ref "U4") (pin "26") (pinfunction "PB13_26") (pintype "bidirectional"))
    )
    (net (code "85") (name "unconnected-(U4-PB14-Pad27)") (class "Default")
      (node (ref "U4") (pin "27") (pinfunction "PB14_27") (pintype "bidirectional"))
    )
    (net (code "86") (name "unconnected-(U4-PC13-ANTI_TAMP-Pad2)") (class "Default")
      (node (ref "U4") (pin "2") (pinfunction "PC13-ANTI_TAMP_2") (pintype "bidirectional"))
    )
    (net (code "87") (name "unconnected-(U4-PC14-OSC32_IN-Pad3)") (class "Default")
      (node (ref "U4") (pin "3") (pinfunction "PC14-OSC32_IN_3") (pintype "bidirectional"))
    )
    (net (code "88") (name "unconnected-(U4-PC15-OSC32_OUT-Pad4)") (class "Default")
      (node (ref "U4") (pin "4") (pinfunction "PC15-OSC32_OUT_4") (pintype "bidirectional"))
    )
    (net (code "89") (name "unconnected-(U4-PH0-OSC_IN-Pad5)") (class "Default")
      (node (ref "U4") (pin "5") (pinfunction "PH0-OSC_IN_5") (pintype "bidirectional"))
    )
    (net (code "90") (name "unconnected-(U4-PH1-OSC_OUT-Pad6)") (class "Default")
      (node (ref "U4") (pin "6") (pinfunction "PH1-OSC_OUT_6") (pintype "bidirectional"))
    )
    (net (code "91") (name "unconnected-(U5-AD0{slash}DIO0-Pad33)") (class "Default")
      (node (ref "U5") (pin "33") (pinfunction "AD0/DIO0_33") (pintype "bidirectional+no_connect"))
    )
    (net (code "92") (name "unconnected-(U5-AD1{slash}DIO1-Pad32)") (class "Default")
      (node (ref "U5") (pin "32") (pinfunction "AD1/DIO1_32") (pintype "bidirectional+no_connect"))
    )
    (net (code "93") (name "unconnected-(U5-AD2{slash}DIO2-Pad31)") (class "Default")
      (node (ref "U5") (pin "31") (pinfunction "AD2/DIO2_31") (pintype "bidirectional+no_connect"))
    )
    (net (code "94") (name "unconnected-(U5-AD3{slash}DIO3-Pad30)") (class "Default")
      (node (ref "U5") (pin "30") (pinfunction "AD3/DIO3_30") (pintype "bidirectional+no_connect"))
    )
    (net (code "95") (name "unconnected-(U5-ASSOCIATE{slash}DIO5-Pad28)") (class "Default")
      (node (ref "U5") (pin "28") (pinfunction "ASSOCIATE/DIO5_28") (pintype "bidirectional+no_connect"))
    )
    (net (code "96") (name "unconnected-(U5-DIO4-Pad24)") (class "Default")
      (node (ref "U5") (pin "24") (pinfunction "DIO4_24") (pintype "bidirectional+no_connect"))
    )
    (net (code "97") (name "unconnected-(U5-DIO12-Pad5)") (class "Default")
      (node (ref "U5") (pin "5") (pinfunction "DIO12_5") (pintype "bidirectional+no_connect"))
    )
    (net (code "98") (name "unconnected-(U5-ON{slash}~{SLEEP}{slash}DIO9-Pad26)") (class "Default")
      (node (ref "U5") (pin "26") (pinfunction "ON/~{SLEEP}/DIO9_26") (pintype "bidirectional+no_connect"))
    )
    (net (code "99") (name "unconnected-(U5-PWM1{slash}DIO11-Pad8)") (class "Default")
      (node (ref "U5") (pin "8") (pinfunction "PWM1/DIO11_8") (pintype "bidirectional+no_connect"))
    )
    (net (code "100") (name "unconnected-(U5-RESERVED-Pad9)") (class "Default")
      (node (ref "U5") (pin "9") (pinfunction "RESERVED_9") (pintype "passive+no_connect"))
    )
    (net (code "101") (name "unconnected-(U5-RESERVED-Pad18)") (class "Default")
      (node (ref "U5") (pin "18") (pinfunction "RESERVED_18") (pintype "passive+no_connect"))
    )
    (net (code "102") (name "unconnected-(U5-RESERVED-Pad19)") (class "Default")
      (node (ref "U5") (pin "19") (pinfunction "RESERVED_19") (pintype "passive+no_connect"))
    )
    (net (code "103") (name "unconnected-(U5-RESERVED-Pad20)") (class "Default")
      (node (ref "U5") (pin "20") (pinfunction "RESERVED_20") (pintype "passive+no_connect"))
    )
    (net (code "104") (name "unconnected-(U5-RESERVED-Pad21)") (class "Default")
      (node (ref "U5") (pin "21") (pinfunction "RESERVED_21") (pintype "passive+no_connect"))
    )
    (net (code "105") (name "unconnected-(U5-RESERVED-Pad23)") (class "Default")
      (node (ref "U5") (pin "23") (pinfunction "RESERVED_23") (pintype "passive+no_connect"))
    )
    (net (code "106") (name "unconnected-(U5-RESERVED-Pad34)") (class "Default")
      (node (ref "U5") (pin "34") (pinfunction "RESERVED_34") (pintype "passive+no_connect"))
    )
    (net (code "107") (name "unconnected-(U5-RESERVED-Pad37)") (class "Default")
      (node (ref "U5") (pin "37") (pinfunction "RESERVED_37") (pintype "passive+no_connect"))
    )
    (net (code "108") (name "unconnected-(U5-RF-Pad36)") (class "Default")
      (node (ref "U5") (pin "36") (pinfunction "RF_36") (pintype "bidirectional"))
    )
    (net (code "109") (name "unconnected-(U5-RSSI_PWM{slash}DIO10-Pad7)") (class "Default")
      (node (ref "U5") (pin "7") (pinfunction "RSSI_PWM/DIO10_7") (pintype "bidirectional+no_connect"))
    )
    (net (code "110") (name "unconnected-(U5-SPI_CLK{slash}DIO18-Pad14)") (class "Default")
      (node (ref "U5") (pin "14") (pinfunction "SPI_CLK/DIO18_14") (pintype "bidirectional+no_connect"))
    )
    (net (code "111") (name "unconnected-(U5-SPI_MISO{slash}DIO15-Pad17)") (class "Default")
      (node (ref "U5") (pin "17") (pinfunction "SPI_MISO/DIO15_17") (pintype "bidirectional+no_connect"))
    )
    (net (code "112") (name "unconnected-(U5-SPI_MOSI{slash}DIO16-Pad16)") (class "Default")
      (node (ref "U5") (pin "16") (pinfunction "SPI_MOSI/DIO16_16") (pintype "bidirectional+no_connect"))
    )
    (net (code "113") (name "unconnected-(U5-SPI_~{ATTN}{slash}~{BOOTMODE}{slash}DIO19-Pad12)") (class "Default")
      (node (ref "U5") (pin "12") (pinfunction "SPI_~{ATTN}/~{BOOTMODE}/DIO19_12") (pintype "bidirectional+no_connect"))
    )
    (net (code "114") (name "unconnected-(U5-SPI_~{SSEL}{slash}DIO17-Pad15)") (class "Default")
      (node (ref "U5") (pin "15") (pinfunction "SPI_~{SSEL}/DIO17_15") (pintype "bidirectional+no_connect"))
    )
    (net (code "115") (name "unconnected-(U5-VREF-Pad27)") (class "Default")
      (node (ref "U5") (pin "27") (pinfunction "VREF_27") (pintype "input+no_connect"))
    )
    (net (code "116") (name "unconnected-(U5-~{CTS}{slash}DIO7-Pad25)") (class "Default")
      (node (ref "U5") (pin "25") (pinfunction "~{CTS}/DIO7_25") (pintype "bidirectional+no_connect"))
    )
    (net (code "117") (name "unconnected-(U5-~{DTR}{slash}SLEEP_RQ{slash}DIO8-Pad10)") (class "Default")
      (node (ref "U5") (pin "10") (pinfunction "~{DTR}/SLEEP_RQ/DIO8_10") (pintype "bidirectional+no_connect"))
    )
    (net (code "118") (name "unconnected-(U5-~{RESET}-Pad6)") (class "Default")
      (node (ref "U5") (pin "6") (pinfunction "~{RESET}_6") (pintype "input+no_connect"))
    )
    (net (code "119") (name "unconnected-(U5-~{RTS}{slash}DIO6-Pad29)") (class "Default")
      (node (ref "U5") (pin "29") (pinfunction "~{RTS}/DIO6_29") (pintype "bidirectional+no_connect"))
    )
    (net (code "120") (name "unconnected-(U6A-32kHz-Pad1)") (class "Default")
      (node (ref "U6") (pin "1") (pinfunction "32kHz_1") (pintype "open_collector+no_connect"))
    )
    (net (code "121") (name "unconnected-(U6A-VBAT-Pad14)") (class "Default")
      (node (ref "U6") (pin "14") (pinfunction "VBAT_14") (pintype "power_in+no_connect"))
    )
    (net (code "122") (name "unconnected-(U6A-~{INT}{slash}SQW-Pad3)") (class "Default")
      (node (ref "U6") (pin "3") (pinfunction "~{INT}/SQW_3") (pintype "open_collector+no_connect"))
    )
    (net (code "123") (name "unconnected-(U6A-~{RST}-Pad4)") (class "Default")
      (node (ref "U6") (pin "4") (pinfunction "~{RST}_4") (pintype "bidirectional+no_connect"))
    )
  )
)
